# PSU_Schematic.net
KiCad netlist of a schematic drawn in Altium Designer
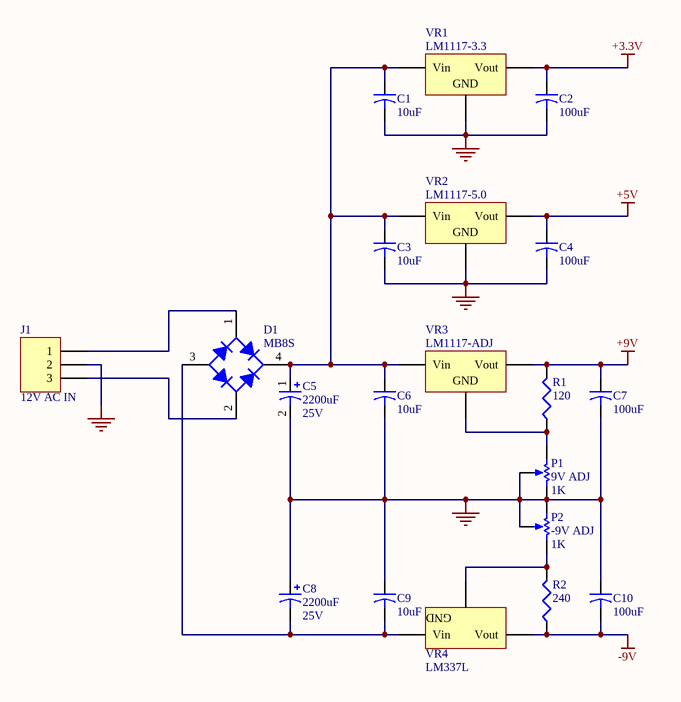
[diagram p0: PSU.Schematic.SchDoc]

(export (version "E")
  (design (tool "Eeschema 10.0.6"))
  (components
    (comp (ref "C1")
      (value "10uF")
      (footprint "CAPC1608N")
      (description "Capacitor")
      (fields (field (name "PUBLISHER") "Altium Limited"))
      (libsource (lib "Miscellaneous Devices") (part "Cap2"))
    )
    (comp (ref "C2")
      (value "100uF")
      (footprint "CAPC1608N")
      (description "Capacitor")
      (fields (field (name "PUBLISHER") "Altium Limited"))
      (libsource (lib "Miscellaneous Devices") (part "Cap2"))
    )
    (comp (ref "C3")
      (value "10uF")
      (footprint "CAPC1608N")
      (description "Capacitor")
      (fields (field (name "PUBLISHER") "Altium Limited"))
      (libsource (lib "Miscellaneous Devices") (part "Cap2"))
    )
    (comp (ref "C4")
      (value "100uF")
      (footprint "CAPC1608N")
      (description "Capacitor")
      (fields (field (name "PUBLISHER") "Altium Limited"))
      (libsource (lib "Miscellaneous Devices") (part "Cap2"))
    )
    (comp (ref "C5")
      (value "2200uF")
      (footprint "Condo electro 13")
      (description "Polarized Capacitor (Radial)")
      (fields (field (name "ALTIUM_VALUE") "25V") (field (name "PUBLISHER") "Altium Limited"))
      (libsource (lib "") (part "Cap Pol1_1"))
    )
    (comp (ref "C6")
      (value "10uF")
      (footprint "CAPC1608N")
      (description "Capacitor")
      (fields (field (name "PUBLISHER") "Altium Limited"))
      (libsource (lib "Miscellaneous Devices") (part "Cap2"))
    )
    (comp (ref "C7")
      (value "100uF")
      (footprint "CAPC1608N")
      (description "Capacitor")
      (fields (field (name "PUBLISHER") "Altium Limited"))
      (libsource (lib "Miscellaneous Devices") (part "Cap2"))
    )
    (comp (ref "C8")
      (value "2200uF")
      (footprint "Condo electro 13")
      (description "Polarized Capacitor (Radial)")
      (fields (field (name "ALTIUM_VALUE") "25V") (field (name "PUBLISHER") "Altium Limited"))
      (libsource (lib "Miscellaneous Devices") (part "Cap Pol1"))
    )
    (comp (ref "C9")
      (value "10uF")
      (footprint "CAPC1608N")
      (description "Capacitor")
      (fields (field (name "PUBLISHER") "Altium Limited"))
      (libsource (lib "Miscellaneous Devices") (part "Cap2"))
    )
    (comp (ref "C10")
      (value "100uF")
      (footprint "CAPC1608N")
      (description "Capacitor")
      (fields (field (name "PUBLISHER") "Altium Limited"))
      (libsource (lib "Miscellaneous Devices") (part "Cap2"))
    )
    (comp (ref "D1")
      (value "MB8S")
      (footprint "MB8S")
      (description "Full Wave Diode Bridge")
      (fields (field (name "PUBLISHER") "Altium Limited"))
      (libsource (lib "Miscellaneous Devices") (part "Bridge1"))
    )
    (comp (ref "J1")
      (value "12V AC IN")
      (footprint "NEB 21 R")
      (description "Header, 3-Pin")
      (fields (field (name "PUBLISHER") "Altium Limited"))
      (libsource (lib "Miscellaneous Connectors") (part "Header 3"))
    )
    (comp (ref "P1")
      (value "9V ADJ")
      (footprint "BOURNS Trim pot")
      (description "Potentiometer")
      (fields (field (name "ALTIUM_VALUE") "1K") (field (name "PUBLISHER") "Altium Limited"))
      (libsource (lib "Miscellaneous Devices") (part "RPot"))
    )
    (comp (ref "P2")
      (value "-9V ADJ")
      (footprint "BOURNS Trim pot")
      (description "Potentiometer")
      (fields (field (name "ALTIUM_VALUE") "1K") (field (name "PUBLISHER") "Altium Limited"))
      (libsource (lib "Miscellaneous Devices") (part "RPot"))
    )
    (comp (ref "R1")
      (value "120")
      (footprint "CAPC1608N")
      (description "Resistor")
      (fields (field (name "PUBLISHER") "Altium Limited"))
      (libsource (lib "Miscellaneous Devices") (part "Res3"))
    )
    (comp (ref "R2")
      (value "240")
      (footprint "CAPC1608N")
      (description "Resistor")
      (fields (field (name "PUBLISHER") "Altium Limited"))
      (libsource (lib "Miscellaneous Devices") (part "Res3"))
    )
    (comp (ref "VR1")
      (value "LM1117-3.3")
      (footprint "LM1117-SOT")
      (description "Voltage Regulator")
      (fields (field (name "PUBLISHER") "Altium Limited"))
      (libsource (lib "Miscellaneous Devices") (part "Volt Reg"))
    )
    (comp (ref "VR2")
      (value "LM1117-5.0")
      (footprint "LM1117-SOT")
      (description "Voltage Regulator")
      (fields (field (name "PUBLISHER") "Altium Limited"))
      (libsource (lib "Miscellaneous Devices") (part "Volt Reg"))
    )
    (comp (ref "VR3")
      (value "LM1117-ADJ")
      (footprint "LM1117-SOT")
      (description "Voltage Regulator")
      (fields (field (name "PUBLISHER") "Altium Limited"))
      (libsource (lib "Miscellaneous Devices") (part "Volt Reg"))
    )
    (comp (ref "VR4")
      (value "LM337L")
      (footprint "LM337L")
      (description "Voltage Regulator")
      (fields (field (name "PUBLISHER") "Altium Limited"))
      (libsource (lib "") (part "Volt Reg_1"))
    )
  )
  (nets
    (net (code "1") (name "+3.3V") (class "Default")
      (node (ref "C2") (pin "1") (pinfunction "1_1") (pintype "passive"))
      (node (ref "VR1") (pin "3") (pinfunction "Vout_3") (pintype "passive"))
    )
    (net (code "2") (name "+5V") (class "Default")
      (node (ref "C4") (pin "1") (pinfunction "1_1") (pintype "passive"))
      (node (ref "VR2") (pin "3") (pinfunction "Vout_3") (pintype "passive"))
    )
    (net (code "3") (name "+9V") (class "Default")
      (node (ref "C7") (pin "1") (pinfunction "1_1") (pintype "passive"))
      (node (ref "R1") (pin "2") (pinfunction "2_2") (pintype "passive"))
      (node (ref "VR3") (pin "3") (pinfunction "Vout_3") (pintype "passive"))
    )
    (net (code "4") (name "-9V") (class "Default")
      (node (ref "C10") (pin "2") (pinfunction "2_2") (pintype "passive"))
      (node (ref "R2") (pin "1") (pinfunction "1_1") (pintype "passive"))
      (node (ref "VR4") (pin "3") (pinfunction "Vout_3") (pintype "passive"))
    )
    (net (code "5") (name "GND") (class "Default")
      (node (ref "C1") (pin "2") (pinfunction "2_2") (pintype "passive"))
      (node (ref "C10") (pin "1") (pinfunction "1_1") (pintype "passive"))
      (node (ref "C2") (pin "2") (pinfunction "2_2") (pintype "passive"))
      (node (ref "C3") (pin "2") (pinfunction "2_2") (pintype "passive"))
      (node (ref "C4") (pin "2") (pinfunction "2_2") (pintype "passive"))
      (node (ref "C5") (pin "2") (pinfunction "2_2") (pintype "passive"))
      (node (ref "C6") (pin "2") (pinfunction "2_2") (pintype "passive"))
      (node (ref "C7") (pin "2") (pinfunction "2_2") (pintype "passive"))
      (node (ref "C8") (pin "1") (pinfunction "1_1") (pintype "passive"))
      (node (ref "C9") (pin "1") (pinfunction "1_1") (pintype "passive"))
      (node (ref "J1") (pin "2") (pinfunction "2_2") (pintype "passive"))
      (node (ref "P1") (pin "1") (pinfunction "TOP_1") (pintype "passive"))
      (node (ref "P1") (pin "3") (pinfunction "TAP_3") (pintype "passive"))
      (node (ref "P2") (pin "2") (pinfunction "BOT_2") (pintype "passive"))
      (node (ref "P2") (pin "3") (pinfunction "TAP_3") (pintype "passive"))
      (node (ref "VR1") (pin "2") (pinfunction "GND_2") (pintype "passive"))
      (node (ref "VR2") (pin "2") (pinfunction "GND_2") (pintype "passive"))
    )
    (net (code "6") (name "Net-(D1-A)") (class "Default")
      (node (ref "C8") (pin "2") (pinfunction "2_2") (pintype "passive"))
      (node (ref "C9") (pin "2") (pinfunction "2_2") (pintype "passive"))
      (node (ref "D1") (pin "3") (pinfunction "A_3") (pintype "passive"))
      (node (ref "VR4") (pin "1") (pinfunction "Vin_1") (pintype "passive"))
    )
    (net (code "7") (name "Net-(D1-C-Pad1)") (class "Default")
      (node (ref "D1") (pin "1") (pinfunction "C_1") (pintype "passive"))
      (node (ref "J1") (pin "1") (pinfunction "1_1") (pintype "passive"))
    )
    (net (code "8") (name "Net-(D1-C-Pad2)") (class "Default")
      (node (ref "D1") (pin "2") (pinfunction "C_2") (pintype "passive"))
      (node (ref "J1") (pin "3") (pinfunction "3_3") (pintype "passive"))
    )
    (net (code "9") (name "Net-(D1-K)") (class "Default")
      (node (ref "C1") (pin "1") (pinfunction "1_1") (pintype "passive"))
      (node (ref "C3") (pin "1") (pinfunction "1_1") (pintype "passive"))
      (node (ref "C5") (pin "1") (pinfunction "1_1") (pintype "passive"))
      (node (ref "C6") (pin "1") (pinfunction "1_1") (pintype "passive"))
      (node (ref "D1") (pin "4") (pinfunction "K_4") (pintype "passive"))
      (node (ref "VR1") (pin "1") (pinfunction "Vin_1") (pintype "passive"))
      (node (ref "VR2") (pin "1") (pinfunction "Vin_1") (pintype "passive"))
      (node (ref "VR3") (pin "1") (pinfunction "Vin_1") (pintype "passive"))
    )
    (net (code "10") (name "Net-(P1-BOT)") (class "Default")
      (node (ref "P1") (pin "2") (pinfunction "BOT_2") (pintype "passive"))
      (node (ref "R1") (pin "1") (pinfunction "1_1") (pintype "passive"))
      (node (ref "VR3") (pin "2") (pinfunction "GND_2") (pintype "passive"))
    )
    (net (code "11") (name "Net-(P2-TOP)") (class "Default")
      (node (ref "P2") (pin "1") (pinfunction "TOP_1") (pintype "passive"))
      (node (ref "R2") (pin "2") (pinfunction "2_2") (pintype "passive"))
      (node (ref "VR4") (pin "2") (pinfunction "ADJ_2") (pintype "passive"))
    )
  )
)
